# HPREF-NOSW.net
KiCad netlist of a schematic drawn in Altium Designer
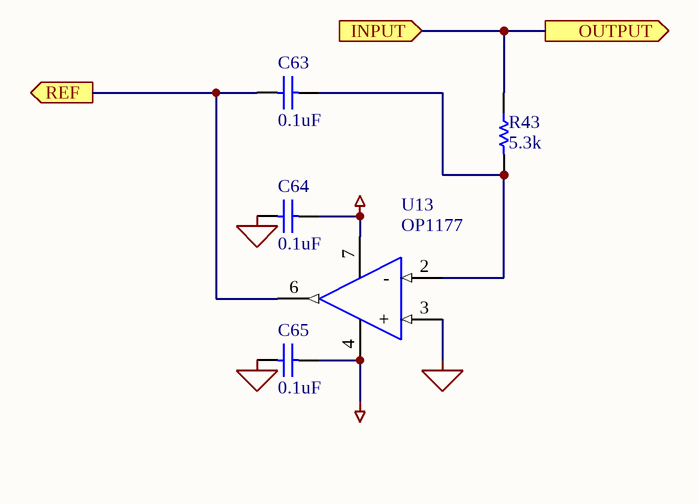
[diagram p0: HPREF-NOSW.SCHDOC]

(export (version "E")
  (design (tool "Eeschema 10.0.6"))
  (components
    (comp (ref "C63")
      (value "0.1uF")
      (footprint "CC3216-1206")
      (description "Capacitor")
      (fields
        (field (name "MANUFACTURER") "Generic Components")
        (field (name "Comment") "Cap")
        (field (name "PUBLISHER") "Altium Limited")
      )
      (libsource (lib "Miscellaneous Devices") (part "Cap"))
    )
    (comp (ref "C64")
      (value "0.1uF")
      (footprint "CC1608-0603")
      (description "Capacitor")
      (fields
        (field (name "MANUFACTURER") "Generic Components")
        (field (name "Comment") "Cap")
        (field (name "PUBLISHER") "Altium Limited")
      )
      (libsource (lib "Miscellaneous Devices") (part "Cap"))
    )
    (comp (ref "C65")
      (value "0.1uF")
      (footprint "CC1608-0603")
      (description "Capacitor")
      (fields
        (field (name "MANUFACTURER") "Generic Components")
        (field (name "Comment") "Cap")
        (field (name "PUBLISHER") "Altium Limited")
      )
      (libsource (lib "Miscellaneous Devices") (part "Cap"))
    )
    (comp (ref "R43")
      (value "5.3k")
      (footprint "CC2012-0805")
      (description "Resistor")
      (fields
        (field (name "MANUFACTURER") "Generic Components")
        (field (name "Comment") "Res1")
        (field (name "PUBLISHER") "Altium Limited")
      )
      (libsource (lib "Miscellaneous Devices") (part "Res1"))
    )
    (comp (ref "U13")
      (value "OP1177")
      (footprint "SO-G8/X.6")
      (description "AD Precision Low Noise, Low Input Bias Current Operational Amplifier")
      (libsource (lib "My devices") (part "OP1177"))
    )
  )
  (nets
    (net (code "1") (name "/INPUT") (class "Default")
      (node (ref "R43") (pin "1") (pinfunction "1_1") (pintype "passive"))
    )
    (net (code "2") (name "/REF") (class "Default")
      (node (ref "C63") (pin "2") (pinfunction "2_2") (pintype "passive"))
      (node (ref "U13") (pin "6") (pinfunction "Out_6") (pintype "output"))
    )
    (net (code "3") (name "AGND") (class "Default")
      (node (ref "C64") (pin "1") (pinfunction "1_1") (pintype "passive"))
      (node (ref "C65") (pin "1") (pinfunction "1_1") (pintype "passive"))
      (node (ref "U13") (pin "3") (pinfunction "+_3") (pintype "input"))
    )
    (net (code "4") (name "AVDD") (class "Default")
      (node (ref "C64") (pin "2") (pinfunction "2_2") (pintype "passive"))
      (node (ref "U13") (pin "7") (pinfunction "+Vs_7") (pintype "power_in"))
    )
    (net (code "5") (name "AVSS") (class "Default")
      (node (ref "C65") (pin "2") (pinfunction "2_2") (pintype "passive"))
      (node (ref "U13") (pin "4") (pinfunction "-Vs_4") (pintype "power_in"))
    )
    (net (code "6") (name "Net-(U13--)") (class "Default")
      (node (ref "C63") (pin "1") (pinfunction "1_1") (pintype "passive"))
      (node (ref "R43") (pin "2") (pinfunction "2_2") (pintype "passive"))
      (node (ref "U13") (pin "2") (pinfunction "-_2") (pintype "input"))
    )
  )
)
